# MovimientoALIM.net
KiCad netlist of a schematic drawn in EAGLE
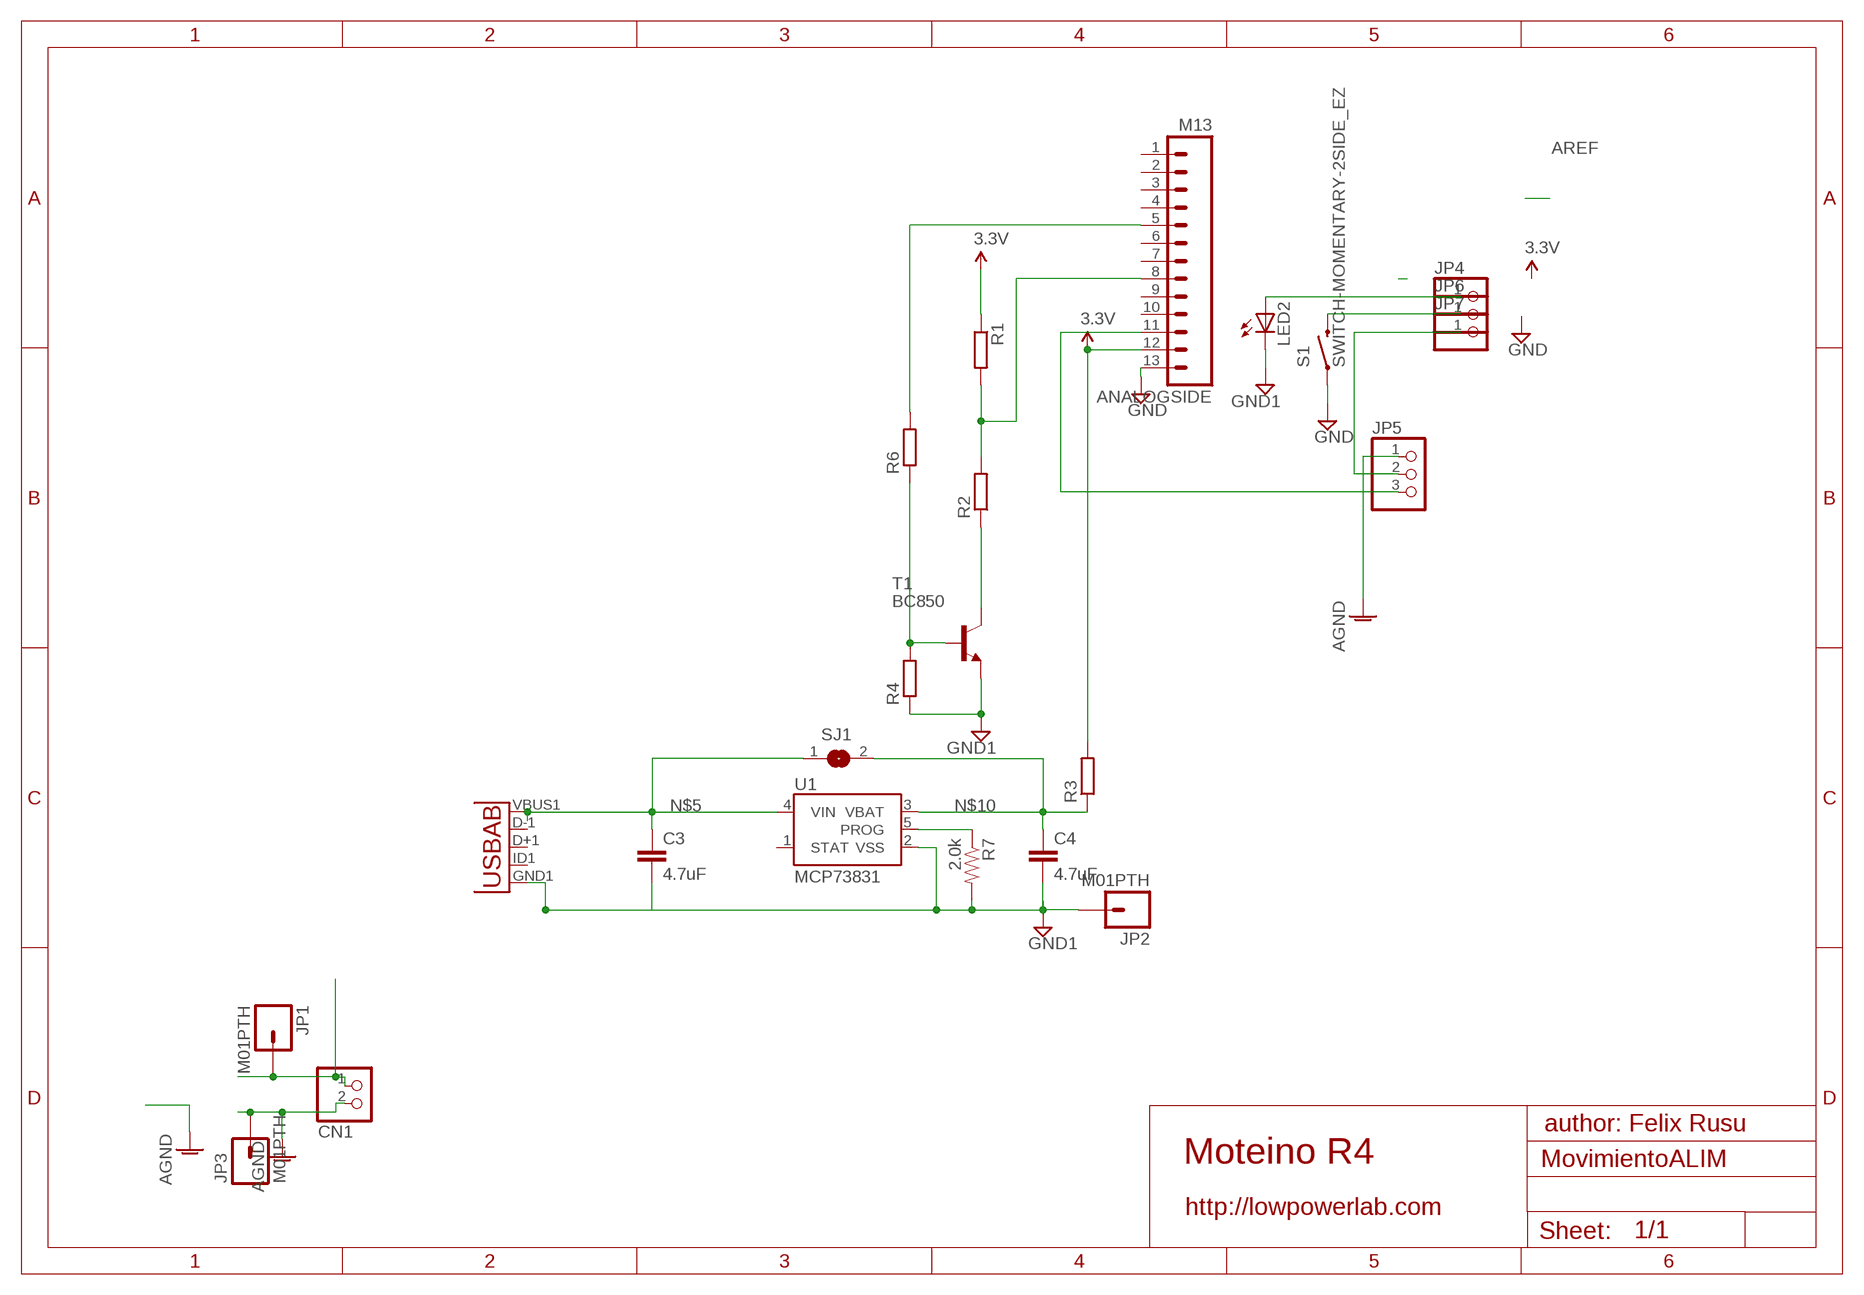
[diagram p0: schematic, sheet 1]

(export (version "E")
  (design (tool "Eeschema 10.0.6"))
  (components
    (comp (ref "ANALOGSIDE")
      (value "M13")
      (footprint "eagle-import:1X13")
      (libsource (lib "eagle-import") (part "M13"))
    )
    (comp (ref "C3")
      (value "4.7uF")
      (footprint "eagle-import:0603-CAP")
      (libsource (lib "eagle-import") (part "4.7UF-6.3V-10%(0603)0603"))
    )
    (comp (ref "C4")
      (value "4.7uF")
      (footprint "eagle-import:0603-CAP")
      (libsource (lib "eagle-import") (part "4.7UF-6.3V-10%(0603)0603"))
    )
    (comp (ref "CN1")
      (value "JST_2PIN-SMT")
      (footprint "eagle-import:JST-PH-2-SMT")
      (libsource (lib "eagle-import") (part "JST_2PIN-SMT"))
    )
    (comp (ref "JP1")
      (value "M01PTH")
      (footprint "eagle-import:1X01")
      (libsource (lib "eagle-import") (part "M01PTH"))
    )
    (comp (ref "JP2")
      (value "M01PTH")
      (footprint "eagle-import:1X01")
      (libsource (lib "eagle-import") (part "M01PTH"))
    )
    (comp (ref "JP3")
      (value "M01PTH")
      (footprint "eagle-import:1X01")
      (libsource (lib "eagle-import") (part "M01PTH"))
    )
    (comp (ref "JP4")
      (value "PINHD-1X1")
      (footprint "eagle-import:1X01")
      (libsource (lib "eagle-import") (part "PINHD-1X1"))
    )
    (comp (ref "JP5")
      (value "PINHD-1X3")
      (footprint "eagle-import:1X03")
      (libsource (lib "eagle-import") (part "PINHD-1X3"))
    )
    (comp (ref "JP6")
      (value "PINHD-1X1")
      (footprint "eagle-import:1X01")
      (libsource (lib "eagle-import") (part "PINHD-1X1"))
    )
    (comp (ref "JP7")
      (value "PINHD-1X1")
      (footprint "eagle-import:1X01")
      (libsource (lib "eagle-import") (part "PINHD-1X1"))
    )
    (comp (ref "JP9")
      (value "Micro USB")
      (footprint "eagle-import:USB-AB-MICRO-SMD_V03")
      (libsource (lib "eagle-import") (part "USB-ABCONN-11794"))
    )
    (comp (ref "LED2")
      (value "LED3MM")
      (footprint "eagle-import:LED3MM")
      (libsource (lib "eagle-import") (part "LED3MM"))
    )
    (comp (ref "R1")
      (value "R-EU_0204/7")
      (footprint "eagle-import:0204_7")
      (libsource (lib "eagle-import") (part "R-EU_0204/7"))
    )
    (comp (ref "R2")
      (value "R-EU_0204/7")
      (footprint "eagle-import:0204_7")
      (libsource (lib "eagle-import") (part "R-EU_0204/7"))
    )
    (comp (ref "R3")
      (value "R-EU_M1206")
      (footprint "eagle-import:M1206")
      (libsource (lib "eagle-import") (part "R-EU_M1206"))
    )
    (comp (ref "R4")
      (value "R-EU_M1206")
      (footprint "eagle-import:M1206")
      (libsource (lib "eagle-import") (part "R-EU_M1206"))
    )
    (comp (ref "R6")
      (value "R-EU_M1206")
      (footprint "eagle-import:M1206")
      (libsource (lib "eagle-import") (part "R-EU_M1206"))
    )
    (comp (ref "R7")
      (value "2.0k")
      (footprint "eagle-import:0603-RES")
      (libsource (lib "eagle-import") (part "2.0KOHM1/10W5%(0603)"))
    )
    (comp (ref "S1")
      (value "SWITCH-MOMENTARY-2SIDE_EZ")
      (footprint "eagle-import:TACTILE-PTH-SIDEEZ")
      (libsource (lib "eagle-import") (part "SWITCH-MOMENTARY-2SIDE_EZ"))
    )
    (comp (ref "SJ1") (value "SJ") (footprint "eagle-import:SJ") (libsource (lib "eagle-import") (part "SJ")))
    (comp (ref "T1")
      (value "BC850")
      (footprint "eagle-import:SOT23")
      (libsource (lib "eagle-import") (part "BC850"))
    )
    (comp (ref "U1")
      (value "MCP73831")
      (footprint "eagle-import:SOT23-5")
      (libsource (lib "eagle-import") (part "MCP73831"))
    )
  )
  (nets
    (net (code "2") (name "/N$5") (class "Default")
      (node (ref "C3") (pin "1") (pinfunction "1_1") (pintype "passive"))
      (node (ref "JP9") (pin "VBUS1") (pinfunction "VBUS_VBUS1") (pintype "bidirectional"))
      (node (ref "SJ1") (pin "1") (pinfunction "1_1") (pintype "passive"))
      (node (ref "U1") (pin "4") (pinfunction "VIN_4") (pintype "power_in"))
    )
    (net (code "3") (name "/N$10") (class "Default")
      (node (ref "C4") (pin "1") (pinfunction "1_1") (pintype "passive"))
      (node (ref "R3") (pin "1") (pinfunction "1_1") (pintype "passive"))
      (node (ref "SJ1") (pin "2") (pinfunction "2_2") (pintype "passive"))
      (node (ref "U1") (pin "3") (pinfunction "VBAT_3") (pintype "power_in"))
    )
    (net (code "4") (name "3.3V") (class "Default")
      (node (ref "ANALOGSIDE") (pin "12") (pinfunction "12_12") (pintype "passive"))
      (node (ref "R1") (pin "1") (pinfunction "1_1") (pintype "passive"))
      (node (ref "R3") (pin "2") (pinfunction "2_2") (pintype "passive"))
    )
    (net (code "5") (name "AGND") (class "Default")
      (node (ref "CN1") (pin "2") (pinfunction "1_2") (pintype "passive"))
      (node (ref "JP3") (pin "1") (pinfunction "1_1") (pintype "passive"))
      (node (ref "JP5") (pin "1") (pinfunction "1_1") (pintype "passive"))
    )
    (net (code "6") (name "GND") (class "Default")
      (node (ref "ANALOGSIDE") (pin "13") (pinfunction "13_13") (pintype "passive"))
      (node (ref "S1") (pin "1") (pinfunction "1_1") (pintype "passive"))
    )
    (net (code "7") (name "GND1") (class "Default")
      (node (ref "C3") (pin "2") (pinfunction "2_2") (pintype "passive"))
      (node (ref "C4") (pin "2") (pinfunction "2_2") (pintype "passive"))
      (node (ref "JP2") (pin "1") (pinfunction "1_1") (pintype "passive"))
      (node (ref "JP9") (pin "GND1") (pinfunction "GND_GND1") (pintype "bidirectional"))
      (node (ref "LED2") (pin "K") (pinfunction "C_K") (pintype "passive"))
      (node (ref "R4") (pin "1") (pinfunction "1_1") (pintype "passive"))
      (node (ref "R7") (pin "2") (pinfunction "2_2") (pintype "passive"))
      (node (ref "T1") (pin "2") (pinfunction "E_2") (pintype "passive"))
      (node (ref "U1") (pin "2") (pinfunction "VSS_2") (pintype "power_in"))
    )
    (net (code "8") (name "Net-(ANALOGSIDE-Pad5)") (class "Default")
      (node (ref "ANALOGSIDE") (pin "5") (pinfunction "5_5") (pintype "passive"))
      (node (ref "R6") (pin "2") (pinfunction "2_2") (pintype "passive"))
    )
    (net (code "9") (name "Net-(ANALOGSIDE-Pad8)") (class "Default")
      (node (ref "ANALOGSIDE") (pin "8") (pinfunction "8_8") (pintype "passive"))
      (node (ref "R1") (pin "2") (pinfunction "2_2") (pintype "passive"))
      (node (ref "R2") (pin "2") (pinfunction "2_2") (pintype "passive"))
    )
    (net (code "10") (name "Net-(ANALOGSIDE-Pad11)") (class "Default")
      (node (ref "ANALOGSIDE") (pin "11") (pinfunction "11_11") (pintype "passive"))
      (node (ref "JP5") (pin "3") (pinfunction "3_3") (pintype "passive"))
    )
    (net (code "11") (name "Net-(CN1-2)") (class "Default")
      (node (ref "CN1") (pin "1") (pinfunction "2_1") (pintype "passive"))
      (node (ref "JP1") (pin "1") (pinfunction "1_1") (pintype "passive"))
    )
    (net (code "12") (name "Net-(JP4-Pad1)") (class "Default")
      (node (ref "JP4") (pin "1") (pinfunction "1_1") (pintype "passive"))
      (node (ref "LED2") (pin "A") (pinfunction "A_A") (pintype "passive"))
    )
    (net (code "13") (name "Net-(JP5-Pad2)") (class "Default")
      (node (ref "JP5") (pin "2") (pinfunction "2_2") (pintype "passive"))
      (node (ref "JP7") (pin "1") (pinfunction "1_1") (pintype "passive"))
    )
    (net (code "14") (name "Net-(JP6-Pad1)") (class "Default")
      (node (ref "JP6") (pin "1") (pinfunction "1_1") (pintype "passive"))
      (node (ref "S1") (pin "2") (pinfunction "2_2") (pintype "passive"))
    )
    (net (code "15") (name "Net-(T1-B)") (class "Default")
      (node (ref "R4") (pin "2") (pinfunction "2_2") (pintype "passive"))
      (node (ref "R6") (pin "1") (pinfunction "1_1") (pintype "passive"))
      (node (ref "T1") (pin "1") (pinfunction "B_1") (pintype "passive"))
    )
    (net (code "16") (name "Net-(T1-C)") (class "Default")
      (node (ref "R2") (pin "1") (pinfunction "1_1") (pintype "passive"))
      (node (ref "T1") (pin "3") (pinfunction "C_3") (pintype "passive"))
    )
    (net (code "17") (name "Net-(U1-PROG)") (class "Default")
      (node (ref "R7") (pin "1") (pinfunction "1_1") (pintype "passive"))
      (node (ref "U1") (pin "5") (pinfunction "PROG_5") (pintype "input"))
    )
    (net (code "18") (name "unconnected-(ANALOGSIDE-Pad1)") (class "Default")
      (node (ref "ANALOGSIDE") (pin "1") (pinfunction "1_1") (pintype "passive"))
    )
    (net (code "19") (name "unconnected-(ANALOGSIDE-Pad2)") (class "Default")
      (node (ref "ANALOGSIDE") (pin "2") (pinfunction "2_2") (pintype "passive"))
    )
    (net (code "20") (name "unconnected-(ANALOGSIDE-Pad3)") (class "Default")
      (node (ref "ANALOGSIDE") (pin "3") (pinfunction "3_3") (pintype "passive"))
    )
    (net (code "21") (name "unconnected-(ANALOGSIDE-Pad4)") (class "Default")
      (node (ref "ANALOGSIDE") (pin "4") (pinfunction "4_4") (pintype "passive"))
    )
    (net (code "22") (name "unconnected-(ANALOGSIDE-Pad6)") (class "Default")
      (node (ref "ANALOGSIDE") (pin "6") (pinfunction "6_6") (pintype "passive"))
    )
    (net (code "23") (name "unconnected-(ANALOGSIDE-Pad7)") (class "Default")
      (node (ref "ANALOGSIDE") (pin "7") (pinfunction "7_7") (pintype "passive"))
    )
    (net (code "24") (name "unconnected-(ANALOGSIDE-Pad9)") (class "Default")
      (node (ref "ANALOGSIDE") (pin "9") (pinfunction "9_9") (pintype "passive"))
    )
    (net (code "25") (name "unconnected-(ANALOGSIDE-Pad10)") (class "Default")
      (node (ref "ANALOGSIDE") (pin "10") (pinfunction "10_10") (pintype "passive"))
    )
    (net (code "26") (name "unconnected-(JP9-D+-PadD+1)") (class "Default")
      (node (ref "JP9") (pin "D+1") (pinfunction "D+_D+1") (pintype "bidirectional"))
    )
    (net (code "27") (name "unconnected-(JP9-D--PadD-1)") (class "Default")
      (node (ref "JP9") (pin "D-1") (pinfunction "D-_D-1") (pintype "bidirectional"))
    )
    (net (code "28") (name "unconnected-(JP9-USBID-PadID1)") (class "Default")
      (node (ref "JP9") (pin "ID1") (pinfunction "USBID_ID1") (pintype "bidirectional"))
    )
    (net (code "29") (name "unconnected-(U1-STAT-Pad1)") (class "Default")
      (node (ref "U1") (pin "1") (pinfunction "STAT_1") (pintype "output"))
    )
  )
)
